# HUD.net
KiCad netlist of a schematic drawn in Altium Designer
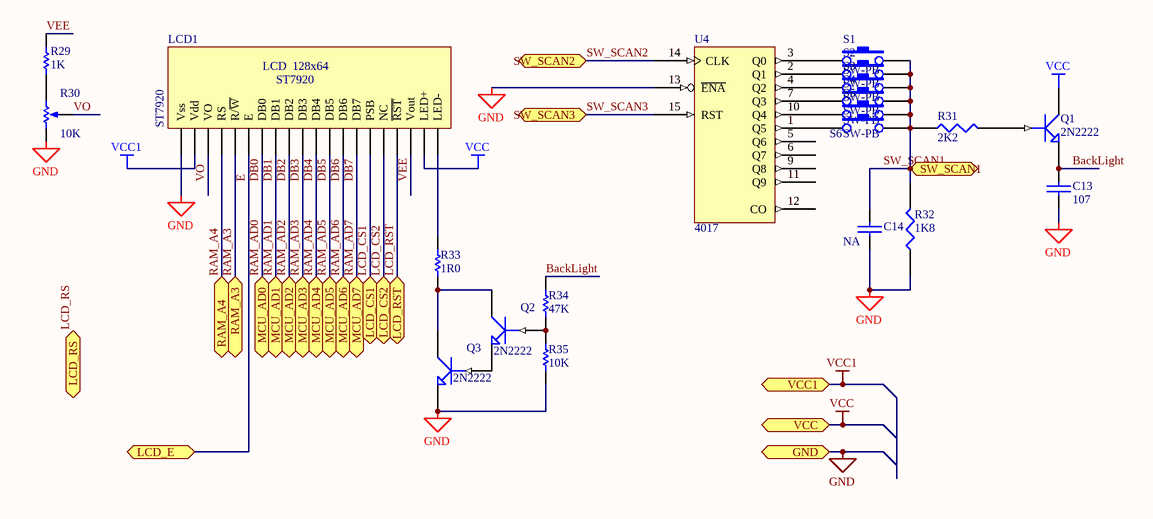
[diagram p0: HUD.SchDoc]

(export (version "E")
  (design (tool "Eeschema 10.0.6"))
  (components
    (comp (ref "C13")
      (value "107")
      (footprint "CAPMP7343X310N")
      (description "Capacitor")
      (libsource (lib "*") (part "CAP"))
    )
    (comp (ref "C14")
      (value "NA")
      (footprint "C6-0805_N")
      (description "Capacitor")
      (libsource (lib "*") (part "CAP"))
    )
    (comp (ref "LCD1")
      (value "ST7920")
      (footprint "LCD12864B")
      (description "ST7920 LCD128X64")
      (libsource (lib "Schlib1") (part "ST7920"))
    )
    (comp (ref "Q1")
      (value "2N2222")
      (footprint "SOT23-3")
      (description "NPN Transistor")
      (libsource (lib "*") (part "NPN1"))
    )
    (comp (ref "Q2")
      (value "2N2222")
      (footprint "SOT23-3")
      (description "NPN Transistor")
      (libsource (lib "*") (part "NPN1"))
    )
    (comp (ref "Q3")
      (value "2N2222")
      (footprint "SOT23-3")
      (description "NPN Transistor")
      (libsource (lib "*") (part "NPN1"))
    )
    (comp (ref "R29")
      (value "1K")
      (footprint "6-0805_N")
      (description "Semiconductor Resistor")
      (fields (field (name "PUBLISHER") "Altium Limited"))
      (libsource (lib "*") (part "Res Semi"))
    )
    (comp (ref "R30")
      (value "10K")
      (footprint "BTXANH")
      (description "Potentiometer")
      (fields (field (name "PUBLISHER") "*"))
      (libsource (lib "*") (part "RPot"))
    )
    (comp (ref "R31") (value "2K2") (footprint "6-0805_N") (libsource (lib "*") (part "RES1")))
    (comp (ref "R32") (value "1K8") (footprint "6-0805_N") (libsource (lib "*") (part "RES1")))
    (comp (ref "R33")
      (value "1R0")
      (footprint "6-0805_N")
      (description "Semiconductor Resistor")
      (fields (field (name "PUBLISHER") "Altium Limited"))
      (libsource (lib "*") (part "Res Semi"))
    )
    (comp (ref "R34")
      (value "47K")
      (footprint "6-0805_N")
      (description "Semiconductor Resistor")
      (fields (field (name "PUBLISHER") "Altium Limited"))
      (libsource (lib "*") (part "Res Semi"))
    )
    (comp (ref "R35")
      (value "10K")
      (footprint "6-0805_N")
      (description "Semiconductor Resistor")
      (fields (field (name "PUBLISHER") "Altium Limited"))
      (libsource (lib "*") (part "Res Semi"))
    )
    (comp (ref "S1") (value "SW-PB") (footprint "CTCHIP_TO") (libsource (lib "*") (part "SW-PB")))
    (comp (ref "S2") (value "SW-PB") (footprint "CTCHIP_TO") (libsource (lib "*") (part "SW-PB")))
    (comp (ref "S3") (value "SW-PB") (footprint "CTCHIP_TO") (libsource (lib "*") (part "SW-PB")))
    (comp (ref "S4") (value "SW-PB") (footprint "CTCHIP_TO") (libsource (lib "*") (part "SW-PB")))
    (comp (ref "S5") (value "SW-PB") (footprint "CTCHIP_TO") (libsource (lib "*") (part "SW-PB")))
    (comp (ref "S6") (value "SW-PB") (footprint "CTCHIP_TO") (libsource (lib "*") (part "SW-PB")))
    (comp (ref "U4") (value "4017") (footprint "SOIC127P600X175-16AN") (libsource (lib "*") (part "4017")))
  )
  (nets
    (net (code "1") (name "/BackLight") (class "Default")
      (node (ref "C13") (pin "1") (pinfunction "1_1") (pintype "passive"))
      (node (ref "Q1") (pin "2") (pinfunction "E_2") (pintype "passive"))
      (node (ref "R34") (pin "2") (pinfunction "2_2") (pintype "passive"))
    )
    (net (code "2") (name "/DB0") (class "Default")
      (node (ref "LCD1") (pin "7") (pinfunction "DB0_7") (pintype "passive"))
    )
    (net (code "3") (name "/DB1") (class "Default")
      (node (ref "LCD1") (pin "8") (pinfunction "DB1_8") (pintype "passive"))
    )
    (net (code "4") (name "/DB2") (class "Default")
      (node (ref "LCD1") (pin "9") (pinfunction "DB2_9") (pintype "passive"))
    )
    (net (code "5") (name "/DB3") (class "Default")
      (node (ref "LCD1") (pin "10") (pinfunction "DB3_10") (pintype "passive"))
    )
    (net (code "6") (name "/DB4") (class "Default")
      (node (ref "LCD1") (pin "11") (pinfunction "DB4_11") (pintype "passive"))
    )
    (net (code "7") (name "/DB5") (class "Default")
      (node (ref "LCD1") (pin "12") (pinfunction "DB5_12") (pintype "passive"))
    )
    (net (code "8") (name "/DB6") (class "Default")
      (node (ref "LCD1") (pin "13") (pinfunction "DB6_13") (pintype "passive"))
    )
    (net (code "9") (name "/DB7") (class "Default")
      (node (ref "LCD1") (pin "14") (pinfunction "DB7_14") (pintype "passive"))
    )
    (net (code "10") (name "/E") (class "Default")
      (node (ref "LCD1") (pin "6") (pinfunction "E_6") (pintype "passive"))
    )
    (net (code "11") (name "/LCD_CS1") (class "Default")
      (node (ref "LCD1") (pin "15") (pinfunction "PSB_15") (pintype "passive"))
    )
    (net (code "12") (name "/LCD_CS2") (class "Default")
      (node (ref "LCD1") (pin "16") (pinfunction "NC_16") (pintype "passive"))
    )
    (net (code "14") (name "/LCD_RST") (class "Default")
      (node (ref "LCD1") (pin "17") (pinfunction "~{RST}_17") (pintype "passive"))
    )
    (net (code "15") (name "/RAM_A3") (class "Default")
      (node (ref "LCD1") (pin "5") (pinfunction "R/~{W}_5") (pintype "passive"))
    )
    (net (code "16") (name "/RAM_A4") (class "Default")
      (node (ref "LCD1") (pin "4") (pinfunction "RS_4") (pintype "passive"))
    )
    (net (code "17") (name "/SW_SCAN1") (class "Default")
      (node (ref "C14") (pin "1") (pinfunction "1_1") (pintype "passive"))
      (node (ref "R31") (pin "1") (pinfunction "1_1") (pintype "passive"))
      (node (ref "R32") (pin "2") (pinfunction "2_2") (pintype "passive"))
      (node (ref "S1") (pin "2") (pinfunction "2_2") (pintype "passive"))
      (node (ref "S2") (pin "2") (pinfunction "2_2") (pintype "passive"))
      (node (ref "S3") (pin "2") (pinfunction "2_2") (pintype "passive"))
      (node (ref "S4") (pin "2") (pinfunction "2_2") (pintype "passive"))
      (node (ref "S5") (pin "2") (pinfunction "2_2") (pintype "passive"))
      (node (ref "S6") (pin "2") (pinfunction "2_2") (pintype "passive"))
    )
    (net (code "18") (name "/SW_SCAN2") (class "Default")
      (node (ref "U4") (pin "14") (pinfunction "CLK_14") (pintype "input"))
    )
    (net (code "19") (name "/SW_SCAN3") (class "Default")
      (node (ref "U4") (pin "15") (pinfunction "RST_15") (pintype "input"))
    )
    (net (code "20") (name "/VEE") (class "Default")
      (node (ref "LCD1") (pin "18") (pinfunction "Vout_18") (pintype "passive"))
      (node (ref "R29") (pin "2") (pinfunction "2_2") (pintype "passive"))
    )
    (net (code "21") (name "/VO") (class "Default")
      (node (ref "LCD1") (pin "3") (pinfunction "VO_3") (pintype "passive"))
      (node (ref "R30") (pin "2") (pinfunction "TAP_2") (pintype "passive"))
    )
    (net (code "22") (name "GND") (class "Default")
      (node (ref "C13") (pin "2") (pinfunction "2_2") (pintype "passive"))
      (node (ref "C14") (pin "2") (pinfunction "2_2") (pintype "passive"))
      (node (ref "LCD1") (pin "1") (pinfunction "Vss_1") (pintype "passive"))
      (node (ref "Q3") (pin "2") (pinfunction "E_2") (pintype "passive"))
      (node (ref "R30") (pin "1") (pinfunction "TOP_1") (pintype "passive"))
      (node (ref "R32") (pin "1") (pinfunction "1_1") (pintype "passive"))
      (node (ref "R35") (pin "1") (pinfunction "1_1") (pintype "passive"))
      (node (ref "U4") (pin "13") (pinfunction "~{ENA}_13") (pintype "input"))
      (node (ref "U4") (pin "8") (pinfunction "GND_8") (pintype "power_in"))
    )
    (net (code "23") (name "Net-(LCD1-LED-)") (class "Default")
      (node (ref "LCD1") (pin "20") (pinfunction "LED-_20") (pintype "passive"))
      (node (ref "R33") (pin "2") (pinfunction "2_2") (pintype "passive"))
    )
    (net (code "24") (name "Net-(Q1-B)") (class "Default")
      (node (ref "Q1") (pin "1") (pinfunction "B_1") (pintype "input"))
      (node (ref "R31") (pin "2") (pinfunction "2_2") (pintype "passive"))
    )
    (net (code "25") (name "Net-(Q2-B)") (class "Default")
      (node (ref "Q2") (pin "1") (pinfunction "B_1") (pintype "input"))
      (node (ref "R34") (pin "1") (pinfunction "1_1") (pintype "passive"))
      (node (ref "R35") (pin "2") (pinfunction "2_2") (pintype "passive"))
    )
    (net (code "26") (name "Net-(Q2-C)") (class "Default")
      (node (ref "Q2") (pin "3") (pinfunction "C_3") (pintype "passive"))
      (node (ref "Q3") (pin "3") (pinfunction "C_3") (pintype "passive"))
      (node (ref "R33") (pin "1") (pinfunction "1_1") (pintype "passive"))
    )
    (net (code "27") (name "Net-(Q2-E)") (class "Default")
      (node (ref "Q2") (pin "2") (pinfunction "E_2") (pintype "passive"))
      (node (ref "Q3") (pin "1") (pinfunction "B_1") (pintype "input"))
    )
    (net (code "28") (name "Net-(R30-BOT)") (class "Default")
      (node (ref "R29") (pin "1") (pinfunction "1_1") (pintype "passive"))
      (node (ref "R30") (pin "3") (pinfunction "BOT_3") (pintype "passive"))
    )
    (net (code "29") (name "Net-(U4-Q0)") (class "Default")
      (node (ref "S1") (pin "1") (pinfunction "1_1") (pintype "passive"))
      (node (ref "U4") (pin "3") (pinfunction "Q0_3") (pintype "output"))
    )
    (net (code "30") (name "Net-(U4-Q1)") (class "Default")
      (node (ref "S2") (pin "1") (pinfunction "1_1") (pintype "passive"))
      (node (ref "U4") (pin "2") (pinfunction "Q1_2") (pintype "output"))
    )
    (net (code "31") (name "Net-(U4-Q2)") (class "Default")
      (node (ref "S3") (pin "1") (pinfunction "1_1") (pintype "passive"))
      (node (ref "U4") (pin "4") (pinfunction "Q2_4") (pintype "output"))
    )
    (net (code "32") (name "Net-(U4-Q3)") (class "Default")
      (node (ref "S4") (pin "1") (pinfunction "1_1") (pintype "passive"))
      (node (ref "U4") (pin "7") (pinfunction "Q3_7") (pintype "output"))
    )
    (net (code "33") (name "Net-(U4-Q4)") (class "Default")
      (node (ref "S5") (pin "1") (pinfunction "1_1") (pintype "passive"))
      (node (ref "U4") (pin "10") (pinfunction "Q4_10") (pintype "output"))
    )
    (net (code "34") (name "Net-(U4-Q5)") (class "Default")
      (node (ref "S6") (pin "1") (pinfunction "1_1") (pintype "passive"))
      (node (ref "U4") (pin "1") (pinfunction "Q5_1") (pintype "output"))
    )
    (net (code "35") (name "VCC") (class "Default")
      (node (ref "LCD1") (pin "19") (pinfunction "LED+_19") (pintype "passive"))
      (node (ref "Q1") (pin "3") (pinfunction "C_3") (pintype "passive"))
      (node (ref "U4") (pin "16") (pinfunction "VCC_16") (pintype "power_in"))
    )
    (net (code "36") (name "VCC1") (class "Default")
      (node (ref "LCD1") (pin "2") (pinfunction "Vdd_2") (pintype "passive"))
    )
    (net (code "37") (name "unconnected-(U4-CO-Pad12)") (class "Default")
      (node (ref "U4") (pin "12") (pinfunction "CO_12") (pintype "output"))
    )
    (net (code "38") (name "unconnected-(U4-Q6-Pad5)") (class "Default")
      (node (ref "U4") (pin "5") (pinfunction "Q6_5") (pintype "output"))
    )
    (net (code "39") (name "unconnected-(U4-Q7-Pad6)") (class "Default")
      (node (ref "U4") (pin "6") (pinfunction "Q7_6") (pintype "output"))
    )
    (net (code "40") (name "unconnected-(U4-Q8-Pad9)") (class "Default")
      (node (ref "U4") (pin "9") (pinfunction "Q8_9") (pintype "output"))
    )
    (net (code "41") (name "unconnected-(U4-Q9-Pad11)") (class "Default")
      (node (ref "U4") (pin "11") (pinfunction "Q9_11") (pintype "output"))
    )
  )
)
